# R409X.net
KiCad netlist of a schematic drawn in EAGLE
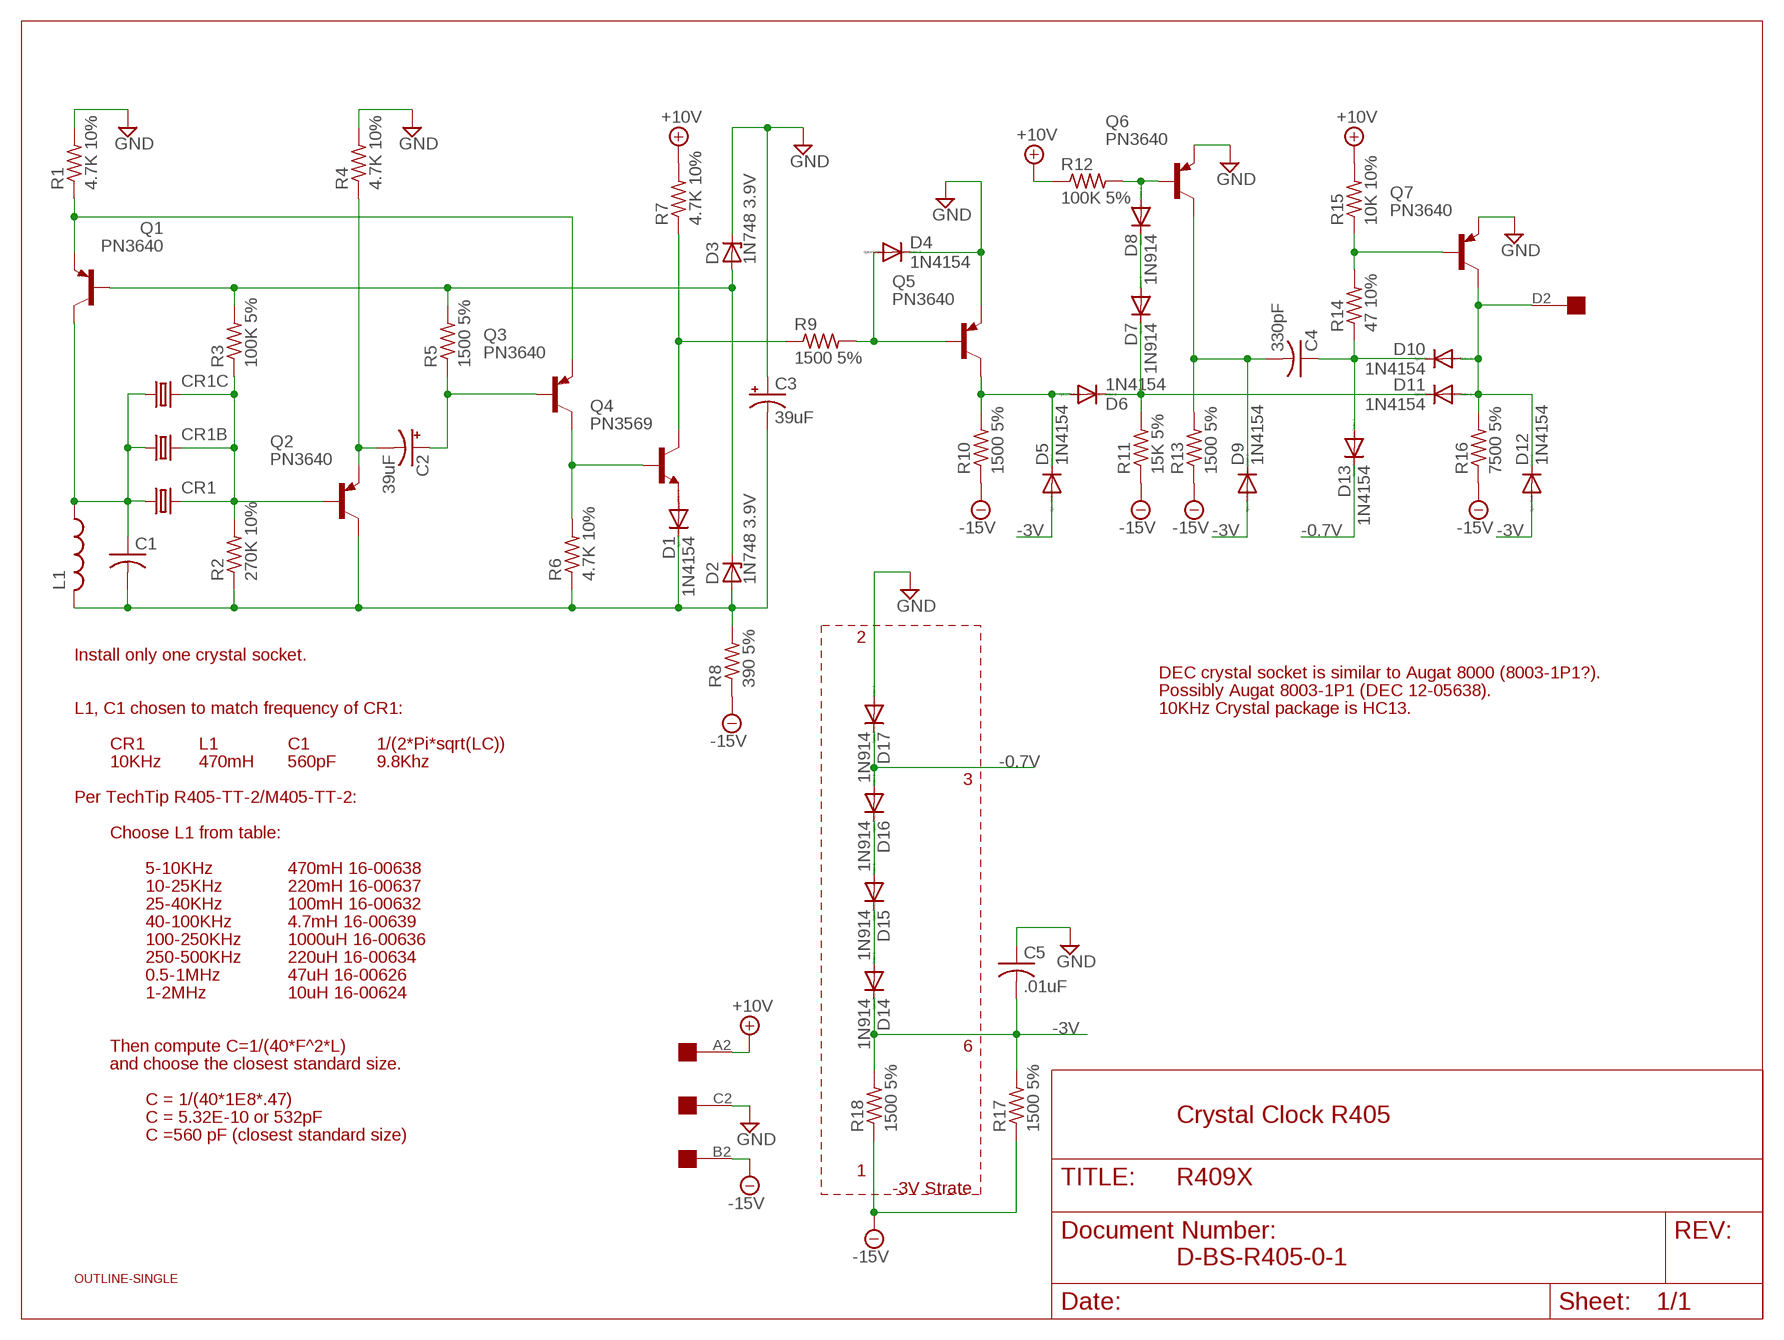
[diagram p0: schematic, sheet 1]

(export (version "E")
  (design (tool "Eeschema 10.0.6"))
  (components
    (comp (ref "C1")
      (value "C-US150-054X183")
      (footprint "eagle-import:C150-054X183")
      (libsource (lib "eagle-import") (part "C-US150-054X183"))
    )
    (comp (ref "C2")
      (value "39uF")
      (footprint "eagle-import:E15-5")
      (libsource (lib "eagle-import") (part "CPOL-USE15-5AXIAL"))
    )
    (comp (ref "C3")
      (value "39uF")
      (footprint "eagle-import:E15-5")
      (libsource (lib "eagle-import") (part "CPOL-USE15-5AXIAL"))
    )
    (comp (ref "C4")
      (value "330pF")
      (footprint "eagle-import:C150-054X183")
      (libsource (lib "eagle-import") (part "C-US150-054X183"))
    )
    (comp (ref "C5")
      (value ".01uF")
      (footprint "eagle-import:C150-054X183")
      (libsource (lib "eagle-import") (part "C-US150-054X183"))
    )
    (comp (ref "CR1")
      (value "CRYSTALHC13U-H")
      (footprint "eagle-import:HC13U-H")
      (libsource (lib "eagle-import") (part "CRYSTALHC13U-H"))
    )
    (comp (ref "CR1B")
      (value "CRYSTALSMALL")
      (footprint "eagle-import:AUG8004")
      (libsource (lib "eagle-import") (part "CRYSTALSMALL"))
    )
    (comp (ref "CR1C")
      (value "CRYSTALBIG")
      (footprint "eagle-import:AUG8000")
      (libsource (lib "eagle-import") (part "CRYSTALBIG"))
    )
    (comp (ref "D1")
      (value "1N4154")
      (footprint "eagle-import:DO35-10")
      (libsource (lib "eagle-import") (part "1N4148DO35-10"))
    )
    (comp (ref "D2")
      (value "1N748 3.9V")
      (footprint "eagle-import:DO35Z10")
      (libsource (lib "eagle-import") (part "ZENER-DIODEDO35Z10"))
    )
    (comp (ref "D3")
      (value "1N748 3.9V")
      (footprint "eagle-import:DO35Z10")
      (libsource (lib "eagle-import") (part "ZENER-DIODEDO35Z10"))
    )
    (comp (ref "D4")
      (value "1N4154")
      (footprint "eagle-import:DO35-10")
      (libsource (lib "eagle-import") (part "1N4148DO35-10"))
    )
    (comp (ref "D5")
      (value "1N4154")
      (footprint "eagle-import:DO35-10")
      (libsource (lib "eagle-import") (part "1N4148DO35-10"))
    )
    (comp (ref "D6")
      (value "1N4154")
      (footprint "eagle-import:DO35-10")
      (libsource (lib "eagle-import") (part "1N4148DO35-10"))
    )
    (comp (ref "D7")
      (value "1N914")
      (footprint "eagle-import:DO35-10")
      (libsource (lib "eagle-import") (part "1N4148DO35-10"))
    )
    (comp (ref "D8")
      (value "1N914")
      (footprint "eagle-import:DO35-10")
      (libsource (lib "eagle-import") (part "1N4148DO35-10"))
    )
    (comp (ref "D9")
      (value "1N4154")
      (footprint "eagle-import:DO35-10")
      (libsource (lib "eagle-import") (part "1N4148DO35-10"))
    )
    (comp (ref "D10")
      (value "1N4154")
      (footprint "eagle-import:DO35-10")
      (libsource (lib "eagle-import") (part "1N4148DO35-10"))
    )
    (comp (ref "D11")
      (value "1N4154")
      (footprint "eagle-import:DO35-10")
      (libsource (lib "eagle-import") (part "1N4148DO35-10"))
    )
    (comp (ref "D12")
      (value "1N4154")
      (footprint "eagle-import:DO35-10")
      (libsource (lib "eagle-import") (part "1N4148DO35-10"))
    )
    (comp (ref "D13")
      (value "1N4154")
      (footprint "eagle-import:DO35-10")
      (libsource (lib "eagle-import") (part "1N4148DO35-10"))
    )
    (comp (ref "D14")
      (value "1N914")
      (footprint "eagle-import:DO35-10")
      (libsource (lib "eagle-import") (part "1N4148DO35-10"))
    )
    (comp (ref "D15")
      (value "1N914")
      (footprint "eagle-import:DO35-10")
      (libsource (lib "eagle-import") (part "1N4148DO35-10"))
    )
    (comp (ref "D16")
      (value "1N914")
      (footprint "eagle-import:DO35-10")
      (libsource (lib "eagle-import") (part "1N4148DO35-10"))
    )
    (comp (ref "D17")
      (value "1N914")
      (footprint "eagle-import:DO35-10")
      (libsource (lib "eagle-import") (part "1N4148DO35-10"))
    )
    (comp (ref "L1")
      (value "L-US0207/7")
      (footprint "eagle-import:0207_7")
      (libsource (lib "eagle-import") (part "L-US0207/7"))
    )
    (comp (ref "Q1")
      (value "PN3640")
      (footprint "eagle-import:TO39")
      (libsource (lib "eagle-import") (part "2N2904"))
    )
    (comp (ref "Q2")
      (value "PN3640")
      (footprint "eagle-import:TO39")
      (libsource (lib "eagle-import") (part "2N2904"))
    )
    (comp (ref "Q3")
      (value "PN3640")
      (footprint "eagle-import:TO39")
      (libsource (lib "eagle-import") (part "2N2904"))
    )
    (comp (ref "Q4")
      (value "PN3569")
      (footprint "eagle-import:TO5")
      (libsource (lib "eagle-import") (part "2N2102"))
    )
    (comp (ref "Q5")
      (value "PN3640")
      (footprint "eagle-import:TO39")
      (libsource (lib "eagle-import") (part "2N2904"))
    )
    (comp (ref "Q6")
      (value "PN3640")
      (footprint "eagle-import:TO39")
      (libsource (lib "eagle-import") (part "2N2904"))
    )
    (comp (ref "Q7")
      (value "PN3640")
      (footprint "eagle-import:TO39")
      (libsource (lib "eagle-import") (part "2N2904"))
    )
    (comp (ref "R1")
      (value "4.7K 10%")
      (footprint "eagle-import:0207_10")
      (libsource (lib "eagle-import") (part "R-US_0207/10"))
    )
    (comp (ref "R2")
      (value "270K 10%")
      (footprint "eagle-import:0207_10")
      (libsource (lib "eagle-import") (part "R-US_0207/10"))
    )
    (comp (ref "R3")
      (value "100K 5%")
      (footprint "eagle-import:0207_10")
      (libsource (lib "eagle-import") (part "R-US_0207/10"))
    )
    (comp (ref "R4")
      (value "4.7K 10%")
      (footprint "eagle-import:0207_10")
      (libsource (lib "eagle-import") (part "R-US_0207/10"))
    )
    (comp (ref "R5")
      (value "1500 5%")
      (footprint "eagle-import:0207_10")
      (libsource (lib "eagle-import") (part "R-US_0207/10"))
    )
    (comp (ref "R6")
      (value "4.7K 10%")
      (footprint "eagle-import:0207_10")
      (libsource (lib "eagle-import") (part "R-US_0207/10"))
    )
    (comp (ref "R7")
      (value "4.7K 10%")
      (footprint "eagle-import:0207_10")
      (libsource (lib "eagle-import") (part "R-US_0207/10"))
    )
    (comp (ref "R8")
      (value "390 5%")
      (footprint "eagle-import:0207_10")
      (libsource (lib "eagle-import") (part "R-US_0207/10"))
    )
    (comp (ref "R9")
      (value "1500 5%")
      (footprint "eagle-import:0207_10")
      (libsource (lib "eagle-import") (part "R-US_0207/10"))
    )
    (comp (ref "R10")
      (value "1500 5%")
      (footprint "eagle-import:0207_10")
      (libsource (lib "eagle-import") (part "R-US_0207/10"))
    )
    (comp (ref "R11")
      (value "15K 5%")
      (footprint "eagle-import:0207_10")
      (libsource (lib "eagle-import") (part "R-US_0207/10"))
    )
    (comp (ref "R12")
      (value "100K 5%")
      (footprint "eagle-import:0207_10")
      (libsource (lib "eagle-import") (part "R-US_0207/10"))
    )
    (comp (ref "R13")
      (value "1500 5%")
      (footprint "eagle-import:0207_10")
      (libsource (lib "eagle-import") (part "R-US_0207/10"))
    )
    (comp (ref "R14")
      (value "47 10%")
      (footprint "eagle-import:0207_10")
      (libsource (lib "eagle-import") (part "R-US_0207/10"))
    )
    (comp (ref "R15")
      (value "10K 10%")
      (footprint "eagle-import:0207_10")
      (libsource (lib "eagle-import") (part "R-US_0207/10"))
    )
    (comp (ref "R16")
      (value "7500 5%")
      (footprint "eagle-import:0207_10")
      (libsource (lib "eagle-import") (part "R-US_0207/10"))
    )
    (comp (ref "R17")
      (value "1500 5%")
      (footprint "eagle-import:0207_10")
      (libsource (lib "eagle-import") (part "R-US_0207/10"))
    )
    (comp (ref "R18")
      (value "1500 5%")
      (footprint "eagle-import:0207_10")
      (libsource (lib "eagle-import") (part "R-US_0207/10"))
    )
    (comp (ref "U$1")
      (value "OUTLINE-SINGLE")
      (footprint "eagle-import:SINGLE")
      (libsource (lib "eagle-import") (part "OUTLINE-SINGLE"))
    )
    (comp (ref "U$2")
      (value "EDGE-1")
      (footprint "eagle-import:EDGE-CON1")
      (libsource (lib "eagle-import") (part "EDGE-1"))
    )
  )
  (nets
    (net (code "1") (name "+10V") (class "Default")
      (node (ref "R12") (pin "1") (pinfunction "1_1") (pintype "passive"))
      (node (ref "R15") (pin "2") (pinfunction "2_2") (pintype "passive"))
      (node (ref "R7") (pin "2") (pinfunction "2_2") (pintype "passive"))
      (node (ref "U$2") (pin "A2") (pinfunction "1_A2") (pintype "bidirectional"))
    )
    (net (code "2") (name "-15V") (class "Default")
      (node (ref "R10") (pin "1") (pinfunction "1_1") (pintype "passive"))
      (node (ref "R11") (pin "1") (pinfunction "1_1") (pintype "passive"))
      (node (ref "R13") (pin "1") (pinfunction "1_1") (pintype "passive"))
      (node (ref "R16") (pin "1") (pinfunction "1_1") (pintype "passive"))
      (node (ref "R17") (pin "1") (pinfunction "1_1") (pintype "passive"))
      (node (ref "R18") (pin "1") (pinfunction "1_1") (pintype "passive"))
      (node (ref "R8") (pin "1") (pinfunction "1_1") (pintype "passive"))
      (node (ref "U$2") (pin "B2") (pinfunction "1_B2") (pintype "bidirectional"))
    )
    (net (code "3") (name "/-0.7V") (class "Default")
      (node (ref "D13") (pin "C") (pinfunction "C_C") (pintype "passive"))
      (node (ref "D16") (pin "A") (pinfunction "A_A") (pintype "passive"))
      (node (ref "D17") (pin "C") (pinfunction "C_C") (pintype "passive"))
    )
    (net (code "4") (name "/-3V") (class "Default")
      (node (ref "C5") (pin "2") (pinfunction "2_2") (pintype "passive"))
      (node (ref "D12") (pin "A") (pinfunction "A_A") (pintype "passive"))
      (node (ref "D14") (pin "C") (pinfunction "C_C") (pintype "passive"))
      (node (ref "D5") (pin "A") (pinfunction "A_A") (pintype "passive"))
      (node (ref "D9") (pin "A") (pinfunction "A_A") (pintype "passive"))
      (node (ref "R17") (pin "2") (pinfunction "2_2") (pintype "passive"))
      (node (ref "R18") (pin "2") (pinfunction "2_2") (pintype "passive"))
    )
    (net (code "5") (name "GND") (class "Default")
      (node (ref "C3") (pin "+") (pinfunction "+_+") (pintype "passive"))
      (node (ref "C5") (pin "1") (pinfunction "1_1") (pintype "passive"))
      (node (ref "D17") (pin "A") (pinfunction "A_A") (pintype "passive"))
      (node (ref "D3") (pin "C") (pinfunction "C_C") (pintype "passive"))
      (node (ref "D4") (pin "C") (pinfunction "C_C") (pintype "passive"))
      (node (ref "Q5") (pin "1") (pinfunction "E_1") (pintype "passive"))
      (node (ref "Q6") (pin "1") (pinfunction "E_1") (pintype "passive"))
      (node (ref "Q7") (pin "1") (pinfunction "E_1") (pintype "passive"))
      (node (ref "R1") (pin "2") (pinfunction "2_2") (pintype "passive"))
      (node (ref "R4") (pin "2") (pinfunction "2_2") (pintype "passive"))
      (node (ref "U$2") (pin "C2") (pinfunction "1_C2") (pintype "bidirectional"))
    )
    (net (code "6") (name "Net-(C4-Pad1)") (class "Default")
      (node (ref "C4") (pin "1") (pinfunction "1_1") (pintype "passive"))
      (node (ref "D10") (pin "C") (pinfunction "C_C") (pintype "passive"))
      (node (ref "D13") (pin "A") (pinfunction "A_A") (pintype "passive"))
      (node (ref "R14") (pin "1") (pinfunction "1_1") (pintype "passive"))
    )
    (net (code "7") (name "Net-(D7-PadA)") (class "Default")
      (node (ref "D7") (pin "A") (pinfunction "A_A") (pintype "passive"))
      (node (ref "D8") (pin "C") (pinfunction "C_C") (pintype "passive"))
    )
    (net (code "8") (name "Net-(D11-PadC)") (class "Default")
      (node (ref "D11") (pin "C") (pinfunction "C_C") (pintype "passive"))
      (node (ref "D6") (pin "C") (pinfunction "C_C") (pintype "passive"))
      (node (ref "D7") (pin "C") (pinfunction "C_C") (pintype "passive"))
      (node (ref "R11") (pin "2") (pinfunction "2_2") (pintype "passive"))
    )
    (net (code "9") (name "Net-(D14-PadA)") (class "Default")
      (node (ref "D14") (pin "A") (pinfunction "A_A") (pintype "passive"))
      (node (ref "D15") (pin "C") (pinfunction "C_C") (pintype "passive"))
    )
    (net (code "10") (name "Net-(D15-PadA)") (class "Default")
      (node (ref "D15") (pin "A") (pinfunction "A_A") (pintype "passive"))
      (node (ref "D16") (pin "C") (pinfunction "C_C") (pintype "passive"))
    )
    (net (code "11") (name "Net-(Q1-B)") (class "Default")
      (node (ref "D2") (pin "C") (pinfunction "C_C") (pintype "passive"))
      (node (ref "D3") (pin "A") (pinfunction "A_A") (pintype "passive"))
      (node (ref "Q1") (pin "2") (pinfunction "B_2") (pintype "passive"))
      (node (ref "R3") (pin "2") (pinfunction "2_2") (pintype "passive"))
      (node (ref "R5") (pin "2") (pinfunction "2_2") (pintype "passive"))
    )
    (net (code "12") (name "Net-(Q1-C)") (class "Default")
      (node (ref "C1") (pin "1") (pinfunction "1_1") (pintype "passive"))
      (node (ref "CR1") (pin "1") (pinfunction "1_1") (pintype "passive"))
      (node (ref "CR1B") (pin "1") (pinfunction "1_1") (pintype "passive"))
      (node (ref "CR1C") (pin "1") (pinfunction "1_1") (pintype "passive"))
      (node (ref "L1") (pin "1") (pinfunction "1_1") (pintype "passive"))
      (node (ref "Q1") (pin "3") (pinfunction "C_3") (pintype "passive"))
    )
    (net (code "13") (name "Net-(Q1-E)") (class "Default")
      (node (ref "Q1") (pin "1") (pinfunction "E_1") (pintype "passive"))
      (node (ref "Q3") (pin "1") (pinfunction "E_1") (pintype "passive"))
      (node (ref "R1") (pin "1") (pinfunction "1_1") (pintype "passive"))
    )
    (net (code "14") (name "Net-(Q2-B)") (class "Default")
      (node (ref "CR1") (pin "2") (pinfunction "2_2") (pintype "passive"))
      (node (ref "CR1B") (pin "2") (pinfunction "2_2") (pintype "passive"))
      (node (ref "CR1C") (pin "2") (pinfunction "2_2") (pintype "passive"))
      (node (ref "Q2") (pin "2") (pinfunction "B_2") (pintype "passive"))
      (node (ref "R2") (pin "2") (pinfunction "2_2") (pintype "passive"))
      (node (ref "R3") (pin "1") (pinfunction "1_1") (pintype "passive"))
    )
    (net (code "15") (name "Net-(Q2-C)") (class "Default")
      (node (ref "C1") (pin "2") (pinfunction "2_2") (pintype "passive"))
      (node (ref "C3") (pin "-") (pinfunction "-_-") (pintype "passive"))
      (node (ref "D1") (pin "C") (pinfunction "C_C") (pintype "passive"))
      (node (ref "D2") (pin "A") (pinfunction "A_A") (pintype "passive"))
      (node (ref "L1") (pin "2") (pinfunction "2_2") (pintype "passive"))
      (node (ref "Q2") (pin "3") (pinfunction "C_3") (pintype "passive"))
      (node (ref "R2") (pin "1") (pinfunction "1_1") (pintype "passive"))
      (node (ref "R6") (pin "1") (pinfunction "1_1") (pintype "passive"))
      (node (ref "R8") (pin "2") (pinfunction "2_2") (pintype "passive"))
    )
    (net (code "16") (name "Net-(Q2-E)") (class "Default")
      (node (ref "C2") (pin "-") (pinfunction "-_-") (pintype "passive"))
      (node (ref "Q2") (pin "1") (pinfunction "E_1") (pintype "passive"))
      (node (ref "R4") (pin "1") (pinfunction "1_1") (pintype "passive"))
    )
    (net (code "17") (name "Net-(Q3-B)") (class "Default")
      (node (ref "C2") (pin "+") (pinfunction "+_+") (pintype "passive"))
      (node (ref "Q3") (pin "2") (pinfunction "B_2") (pintype "passive"))
      (node (ref "R5") (pin "1") (pinfunction "1_1") (pintype "passive"))
    )
    (net (code "18") (name "Net-(Q3-C)") (class "Default")
      (node (ref "Q3") (pin "3") (pinfunction "C_3") (pintype "passive"))
      (node (ref "Q4") (pin "2") (pinfunction "B_2") (pintype "passive"))
      (node (ref "R6") (pin "2") (pinfunction "2_2") (pintype "passive"))
    )
    (net (code "19") (name "Net-(Q4-C)") (class "Default")
      (node (ref "Q4") (pin "3") (pinfunction "C_3") (pintype "passive"))
      (node (ref "R7") (pin "1") (pinfunction "1_1") (pintype "passive"))
      (node (ref "R9") (pin "1") (pinfunction "1_1") (pintype "passive"))
    )
    (net (code "20") (name "Net-(Q4-E)") (class "Default")
      (node (ref "D1") (pin "A") (pinfunction "A_A") (pintype "passive"))
      (node (ref "Q4") (pin "1") (pinfunction "E_1") (pintype "passive"))
    )
    (net (code "21") (name "Net-(Q5-B)") (class "Default")
      (node (ref "D4") (pin "A") (pinfunction "A_A") (pintype "passive"))
      (node (ref "Q5") (pin "2") (pinfunction "B_2") (pintype "passive"))
      (node (ref "R9") (pin "2") (pinfunction "2_2") (pintype "passive"))
    )
    (net (code "22") (name "Net-(Q5-C)") (class "Default")
      (node (ref "D5") (pin "C") (pinfunction "C_C") (pintype "passive"))
      (node (ref "D6") (pin "A") (pinfunction "A_A") (pintype "passive"))
      (node (ref "Q5") (pin "3") (pinfunction "C_3") (pintype "passive"))
      (node (ref "R10") (pin "2") (pinfunction "2_2") (pintype "passive"))
    )
    (net (code "23") (name "Net-(Q6-B)") (class "Default")
      (node (ref "D8") (pin "A") (pinfunction "A_A") (pintype "passive"))
      (node (ref "Q6") (pin "2") (pinfunction "B_2") (pintype "passive"))
      (node (ref "R12") (pin "2") (pinfunction "2_2") (pintype "passive"))
    )
    (net (code "24") (name "Net-(Q6-C)") (class "Default")
      (node (ref "C4") (pin "2") (pinfunction "2_2") (pintype "passive"))
      (node (ref "D9") (pin "C") (pinfunction "C_C") (pintype "passive"))
      (node (ref "Q6") (pin "3") (pinfunction "C_3") (pintype "passive"))
      (node (ref "R13") (pin "2") (pinfunction "2_2") (pintype "passive"))
    )
    (net (code "25") (name "Net-(Q7-B)") (class "Default")
      (node (ref "Q7") (pin "2") (pinfunction "B_2") (pintype "passive"))
      (node (ref "R14") (pin "2") (pinfunction "2_2") (pintype "passive"))
      (node (ref "R15") (pin "1") (pinfunction "1_1") (pintype "passive"))
    )
    (net (code "26") (name "Net-(Q7-C)") (class "Default")
      (node (ref "D10") (pin "A") (pinfunction "A_A") (pintype "passive"))
      (node (ref "D11") (pin "A") (pinfunction "A_A") (pintype "passive"))
      (node (ref "D12") (pin "C") (pinfunction "C_C") (pintype "passive"))
      (node (ref "Q7") (pin "3") (pinfunction "C_3") (pintype "passive"))
      (node (ref "R16") (pin "2") (pinfunction "2_2") (pintype "passive"))
      (node (ref "U$2") (pin "D2") (pinfunction "1_D2") (pintype "bidirectional"))
    )
  )
)
